# pe02.net
KiCad netlist of a schematic drawn in EAGLE
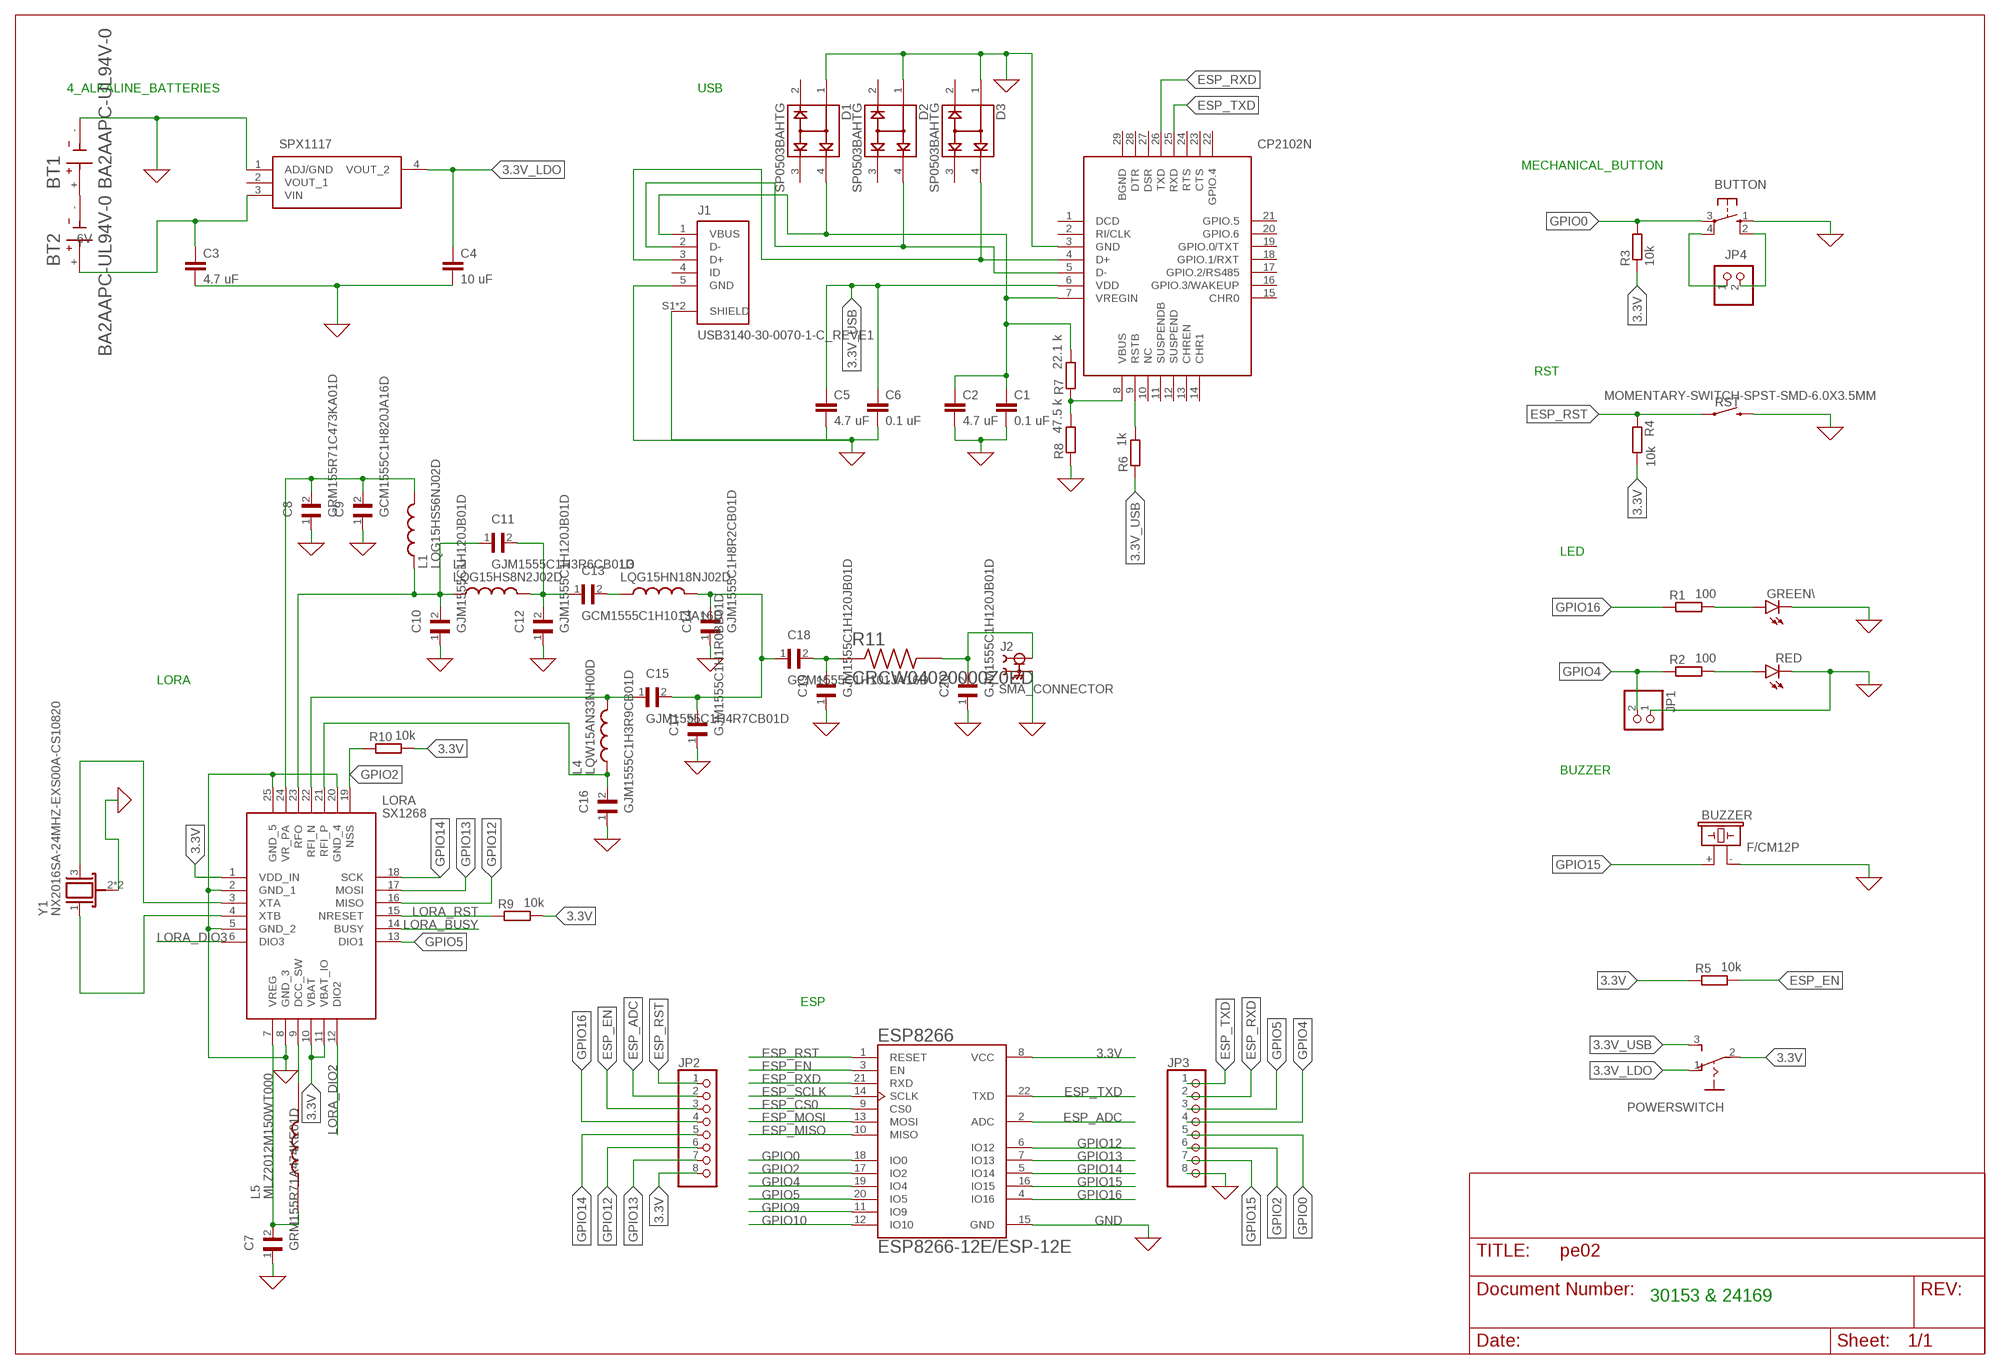
[diagram p0: schematic, sheet 1]

(export (version "E")
  (design (tool "Eeschema 10.0.6"))
  (components
    (comp (ref "BT1")
      (value "BA2AAPC-UL94V-0")
      (footprint "eagle-import:BAT_BA2AAPC-UL94V-0")
      (fields (field (name "MF") "MPD"))
      (libsource (lib "eagle-import") (part "BA2AAPC-UL94V-0"))
    )
    (comp (ref "BT2")
      (value "BA2AAPC-UL94V-0")
      (footprint "eagle-import:BAT_BA2AAPC-UL94V-0")
      (fields (field (name "MF") "MPD"))
      (libsource (lib "eagle-import") (part "BA2AAPC-UL94V-0"))
    )
    (comp (ref "BUTTON")
      (value "10-XX")
      (footprint "eagle-import:B3F-10XX")
      (fields (field (name "MPN") "B3F-1000"))
      (libsource (lib "eagle-import") (part "10-XX"))
    )
    (comp (ref "BUZZER")
      (value "F/CM12P")
      (footprint "eagle-import:F_CM12P")
      (libsource (lib "eagle-import") (part "F/CM12P"))
    )
    (comp (ref "C1")
      (value "0.1 uF")
      (footprint "eagle-import:C1206K")
      (libsource (lib "eagle-import") (part "C-EUC1206K"))
    )
    (comp (ref "C2")
      (value "4.7 uF")
      (footprint "eagle-import:C1206K")
      (libsource (lib "eagle-import") (part "C-EUC1206K"))
    )
    (comp (ref "C3")
      (value "4.7 uF")
      (footprint "eagle-import:C1206K")
      (libsource (lib "eagle-import") (part "C-EUC1206K"))
    )
    (comp (ref "C4")
      (value "10 uF")
      (footprint "eagle-import:C1206K")
      (libsource (lib "eagle-import") (part "C-EUC1206K"))
    )
    (comp (ref "C5")
      (value "4.7 uF")
      (footprint "eagle-import:C1206K")
      (libsource (lib "eagle-import") (part "C-EUC1206K"))
    )
    (comp (ref "C6")
      (value "0.1 uF")
      (footprint "eagle-import:C1206K")
      (libsource (lib "eagle-import") (part "C-EUC1206K"))
    )
    (comp (ref "C7")
      (value "GRM155R71A474KE01D")
      (footprint "eagle-import:CAPC1005X55N")
      (fields (field (name "MF") "Murata"))
      (libsource (lib "eagle-import") (part "GRM155R71A474KE01D"))
    )
    (comp (ref "C8")
      (value "GRM155R71C473KA01D")
      (footprint "eagle-import:CAPC1005X55N")
      (fields (field (name "MF") "Murata"))
      (libsource (lib "eagle-import") (part "GRM155R71C473KA01D"))
    )
    (comp (ref "C9")
      (value "GCM1555C1H820JA16D")
      (footprint "eagle-import:CAPC1005X55N")
      (fields (field (name "MF") "Murata Electronics"))
      (libsource (lib "eagle-import") (part "GCM1555C1H820JA16D"))
    )
    (comp (ref "C10")
      (value "GJM1555C1H120JB01D")
      (footprint "eagle-import:CAPC1005X55N")
      (fields (field (name "MF") "Murata"))
      (libsource (lib "eagle-import") (part "GJM1555C1H120JB01D"))
    )
    (comp (ref "C11")
      (value "GJM1555C1H3R6CB01D")
      (footprint "eagle-import:CAPC1005X55N")
      (fields (field (name "MF") "Murata"))
      (libsource (lib "eagle-import") (part "GJM1555C1H3R6CB01D"))
    )
    (comp (ref "C12")
      (value "GJM1555C1H120JB01D")
      (footprint "eagle-import:CAPC1005X55N")
      (fields (field (name "MF") "Murata"))
      (libsource (lib "eagle-import") (part "GJM1555C1H120JB01D"))
    )
    (comp (ref "C13")
      (value "GCM1555C1H101JA16D")
      (footprint "eagle-import:CAPC1005X55N")
      (fields (field (name "MF") "Murata Electronics"))
      (libsource (lib "eagle-import") (part "GCM1555C1H101JA16D"))
    )
    (comp (ref "C14")
      (value "GJM1555C1H8R2CB01D")
      (footprint "eagle-import:CAPC1005X55N")
      (fields (field (name "MF") "Murata"))
      (libsource (lib "eagle-import") (part "GJM1555C1H8R2CB01D"))
    )
    (comp (ref "C15")
      (value "GJM1555C1H4R7CB01D")
      (footprint "eagle-import:CAPC1005X55N")
      (fields (field (name "MF") "Murata"))
      (libsource (lib "eagle-import") (part "GJM1555C1H4R7CB01D"))
    )
    (comp (ref "C16")
      (value "GJM1555C1H3R9CB01D")
      (footprint "eagle-import:CAPC1005X55N")
      (fields (field (name "MF") "Murata"))
      (libsource (lib "eagle-import") (part "GJM1555C1H3R9CB01D"))
    )
    (comp (ref "C17")
      (value "GJM1555C1H1R0BB01D")
      (footprint "eagle-import:CAPC1005X55N")
      (fields (field (name "MF") "Murata"))
      (libsource (lib "eagle-import") (part "GJM1555C1H1R0BB01D"))
    )
    (comp (ref "C18")
      (value "GCM1555C1H101JA16D")
      (footprint "eagle-import:CAPC1005X55N")
      (fields (field (name "MF") "Murata Electronics"))
      (libsource (lib "eagle-import") (part "GCM1555C1H101JA16D"))
    )
    (comp (ref "C19")
      (value "GJM1555C1H120JB01D")
      (footprint "eagle-import:CAPC1005X55N")
      (fields (field (name "MF") "Murata"))
      (libsource (lib "eagle-import") (part "GJM1555C1H120JB01D"))
    )
    (comp (ref "C20")
      (value "GJM1555C1H120JB01D")
      (footprint "eagle-import:CAPC1005X55N")
      (fields (field (name "MF") "Murata"))
      (libsource (lib "eagle-import") (part "GJM1555C1H120JB01D"))
    )
    (comp (ref "CP2102N")
      (value "CP2102N-A02-GQFN28")
      (footprint "eagle-import:QFN50P500X500X80-29N")
      (fields (field (name "MOUSER_PART_NUMBER") "634-CP2102NA02GQFN28"))
      (libsource (lib "eagle-import") (part "CP2102N-A02-GQFN28"))
    )
    (comp (ref "D1")
      (value "SP0503BAHTG")
      (footprint "eagle-import:SOT143")
      (fields (field (name "MF") "Littelfuse Inc."))
      (libsource (lib "eagle-import") (part "SP0503BAHTG"))
    )
    (comp (ref "D2")
      (value "SP0503BAHTG")
      (footprint "eagle-import:SOT143")
      (fields (field (name "MF") "Littelfuse Inc."))
      (libsource (lib "eagle-import") (part "SP0503BAHTG"))
    )
    (comp (ref "D3")
      (value "SP0503BAHTG")
      (footprint "eagle-import:SOT143")
      (fields (field (name "MF") "Littelfuse Inc."))
      (libsource (lib "eagle-import") (part "SP0503BAHTG"))
    )
    (comp (ref "ESP8266")
      (value "ESP8266-12E/ESP-12E")
      (footprint "eagle-import:XCVR_ESP8266-12E_ESP-12E")
      (fields (field (name "MF") "AI-Thinker"))
      (libsource (lib "eagle-import") (part "ESP8266-12E/ESP-12E"))
    )
    (comp (ref "GREEN\\")
      (value "LEDCHIPLED_1206")
      (footprint "eagle-import:CHIPLED_1206")
      (libsource (lib "eagle-import") (part "LEDCHIPLED_1206"))
    )
    (comp (ref "J1")
      (value "USB3140-30-0070-1-C_REVE1")
      (footprint "eagle-import:GCT_USB3140-30-0070-1-C_REVE1")
      (fields (field (name "MF") "Global Connector Technology") (field (name "MP") "USB3140-30-0070-1-C"))
      (libsource (lib "eagle-import") (part "USB3140-30-0070-1-C_REVE1"))
    )
    (comp (ref "J2")
      (value "SMA_CONNECTOR")
      (footprint "eagle-import:LPRS_SMA_CONNECTOR")
      (fields (field (name "MF") "LPRS") (field (name "MP") "SMA CONNECTOR"))
      (libsource (lib "eagle-import") (part "SMA_CONNECTOR"))
    )
    (comp (ref "JP1")
      (value "PINHD-1X2")
      (footprint "eagle-import:1X02")
      (libsource (lib "eagle-import") (part "PINHD-1X2"))
    )
    (comp (ref "JP2")
      (value "PINHD-1X8")
      (footprint "eagle-import:1X08")
      (libsource (lib "eagle-import") (part "PINHD-1X8"))
    )
    (comp (ref "JP3")
      (value "PINHD-1X8")
      (footprint "eagle-import:1X08")
      (libsource (lib "eagle-import") (part "PINHD-1X8"))
    )
    (comp (ref "JP4")
      (value "PINHD-1X2")
      (footprint "eagle-import:1X02")
      (libsource (lib "eagle-import") (part "PINHD-1X2"))
    )
    (comp (ref "L1")
      (value "LQG15HS56NJ02D")
      (footprint "eagle-import:INDC1005X55N")
      (fields (field (name "MF") "Murata"))
      (libsource (lib "eagle-import") (part "LQG15HS56NJ02D"))
    )
    (comp (ref "L2")
      (value "LQG15HS8N2J02D")
      (footprint "eagle-import:INDC1005X55N")
      (fields (field (name "MF") "Murata"))
      (libsource (lib "eagle-import") (part "LQG15HS8N2J02D"))
    )
    (comp (ref "L3")
      (value "LQG15HN18NJ02D")
      (footprint "eagle-import:INDC1005X55N")
      (fields (field (name "MF") "Murata"))
      (libsource (lib "eagle-import") (part "LQG15HN18NJ02D"))
    )
    (comp (ref "L4")
      (value "LQW15AN33NH00D")
      (footprint "eagle-import:INDC1005X60N")
      (fields (field (name "MF") "Murata"))
      (libsource (lib "eagle-import") (part "LQW15AN33NH00D"))
    )
    (comp (ref "L5")
      (value "MLZ2012M150WT000")
      (footprint "eagle-import:INDC2012X145N")
      (fields (field (name "MF") "TDK Corporation"))
      (libsource (lib "eagle-import") (part "MLZ2012M150WT000"))
    )
    (comp (ref "LORA")
      (value "SX1268")
      (footprint "eagle-import:QFN50P400X400X100-25N")
      (libsource (lib "eagle-import") (part "SX1268"))
    )
    (comp (ref "POWERSWITCH")
      (value "255SB")
      (footprint "eagle-import:255SB")
      (libsource (lib "eagle-import") (part "255SB"))
    )
    (comp (ref "R1")
      (value "100")
      (footprint "eagle-import:R1206")
      (libsource (lib "eagle-import") (part "R-EU_R1206"))
    )
    (comp (ref "R2")
      (value "100")
      (footprint "eagle-import:R1206")
      (libsource (lib "eagle-import") (part "R-EU_R1206"))
    )
    (comp (ref "R3")
      (value "10k")
      (footprint "eagle-import:R1206")
      (libsource (lib "eagle-import") (part "R-EU_R1206"))
    )
    (comp (ref "R4")
      (value "10k")
      (footprint "eagle-import:R1206")
      (libsource (lib "eagle-import") (part "R-EU_R1206"))
    )
    (comp (ref "R5")
      (value "10k")
      (footprint "eagle-import:R1206")
      (libsource (lib "eagle-import") (part "R-EU_R1206"))
    )
    (comp (ref "R6")
      (value "1k")
      (footprint "eagle-import:R1206")
      (libsource (lib "eagle-import") (part "R-EU_R1206"))
    )
    (comp (ref "R7")
      (value "22.1 k")
      (footprint "eagle-import:R1206")
      (libsource (lib "eagle-import") (part "R-EU_R1206"))
    )
    (comp (ref "R8")
      (value "47.5 k")
      (footprint "eagle-import:R1206")
      (libsource (lib "eagle-import") (part "R-EU_R1206"))
    )
    (comp (ref "R9")
      (value "10k")
      (footprint "eagle-import:R1206")
      (libsource (lib "eagle-import") (part "R-EU_R1206"))
    )
    (comp (ref "R10")
      (value "10k")
      (footprint "eagle-import:R1206")
      (libsource (lib "eagle-import") (part "R-EU_R1206"))
    )
    (comp (ref "R11")
      (value "CRCW04020000Z0ED")
      (footprint "eagle-import:RESC1005X40N")
      (fields (field (name "MF") "Vishay"))
      (libsource (lib "eagle-import") (part "CRCW04020000Z0ED"))
    )
    (comp (ref "RED")
      (value "LEDCHIPLED_1206")
      (footprint "eagle-import:CHIPLED_1206")
      (libsource (lib "eagle-import") (part "LEDCHIPLED_1206"))
    )
    (comp (ref "RST")
      (value "MOMENTARY-SWITCH-SPST-SMD-6.0X3.5MM")
      (footprint "eagle-import:TACTILE_SWITCH_SMD_6.0X3.5MM")
      (libsource (lib "eagle-import") (part "MOMENTARY-SWITCH-SPST-SMD-6.0X3.5MM"))
    )
    (comp (ref "SPX1117")
      (value "SPX1117M3-L-3-3_TR")
      (footprint "eagle-import:SOT230P700X180-4N")
      (fields
        (field (name "ARROW_PART_NUMBER") "SPX1117M3-L-3-3/TR")
        (field (name "MOUSER_PART_NUMBER") "701-SPX1117M3-L-33TR")
      )
      (libsource (lib "eagle-import") (part "SPX1117M3-L-3-3_TR"))
    )
    (comp (ref "Y1")
      (value "NX2016SA-24MHZ-EXS00A-CS10820")
      (footprint "eagle-import:OSC_NX2016SA-24MHZ-EXS00A-CS10820")
      (fields (field (name "MF") "NDK America, Inc."))
      (libsource (lib "eagle-import") (part "NX2016SA-24MHZ-EXS00A-CS10820"))
    )
  )
  (nets
    (net (code "1") (name "/6V") (class "Default")
      (node (ref "BT2") (pin "+") (pinfunction "+_+") (pintype "passive"))
      (node (ref "C3") (pin "1") (pinfunction "1_1") (pintype "passive"))
      (node (ref "SPX1117") (pin "3") (pinfunction "VIN_3") (pintype "bidirectional"))
    )
    (net (code "2") (name "/BGND") (class "Default")
      (node (ref "CP2102N") (pin "29") (pinfunction "BGND_29") (pintype "power_in"))
    )
    (net (code "3") (name "/ESP_CS0") (class "Default")
      (node (ref "ESP8266") (pin "9") (pinfunction "CS0_9") (pintype "input"))
    )
    (net (code "4") (name "/ESP_MISO") (class "Default")
      (node (ref "ESP8266") (pin "10") (pinfunction "MISO_10") (pintype "bidirectional"))
    )
    (net (code "5") (name "/ESP_MOSI") (class "Default")
      (node (ref "ESP8266") (pin "13") (pinfunction "MOSI_13") (pintype "bidirectional"))
    )
    (net (code "6") (name "/ESP_SCLK") (class "Default")
      (node (ref "ESP8266") (pin "14") (pinfunction "SCLK_14") (pintype "input"))
    )
    (net (code "7") (name "/GPIO9") (class "Default")
      (node (ref "ESP8266") (pin "11") (pinfunction "IO9_11") (pintype "bidirectional"))
    )
    (net (code "8") (name "/GPIO10") (class "Default")
      (node (ref "ESP8266") (pin "12") (pinfunction "IO10_12") (pintype "bidirectional"))
    )
    (net (code "9") (name "/LORA_BUSY") (class "Default")
      (node (ref "LORA") (pin "14") (pinfunction "BUSY_14") (pintype "bidirectional"))
    )
    (net (code "10") (name "/LORA_DIO2") (class "Default")
      (node (ref "LORA") (pin "12") (pinfunction "DIO2_12") (pintype "bidirectional"))
    )
    (net (code "11") (name "/LORA_DIO3") (class "Default")
      (node (ref "LORA") (pin "6") (pinfunction "DIO3_6") (pintype "bidirectional"))
    )
    (net (code "12") (name "/LORA_RST") (class "Default")
      (node (ref "LORA") (pin "15") (pinfunction "NRESET_15") (pintype "bidirectional"))
      (node (ref "R9") (pin "1") (pinfunction "1_1") (pintype "passive"))
    )
    (net (code "13") (name "3.3V") (class "Default")
      (node (ref "ESP8266") (pin "8") (pinfunction "VCC_8") (pintype "power_in"))
      (node (ref "JP2") (pin "8") (pinfunction "8_8") (pintype "passive"))
      (node (ref "LORA") (pin "1") (pinfunction "VDD_IN_1") (pintype "bidirectional"))
      (node (ref "LORA") (pin "10") (pinfunction "VBAT_10") (pintype "bidirectional"))
      (node (ref "LORA") (pin "11") (pinfunction "VBAT_IO_11") (pintype "bidirectional"))
      (node (ref "POWERSWITCH") (pin "2") (pinfunction "P_2") (pintype "passive"))
      (node (ref "R10") (pin "2") (pinfunction "2_2") (pintype "passive"))
      (node (ref "R3") (pin "1") (pinfunction "1_1") (pintype "passive"))
      (node (ref "R4") (pin "2") (pinfunction "2_2") (pintype "passive"))
      (node (ref "R5") (pin "1") (pinfunction "1_1") (pintype "passive"))
      (node (ref "R9") (pin "2") (pinfunction "2_2") (pintype "passive"))
    )
    (net (code "14") (name "3.3V_LDO") (class "Default")
      (node (ref "C4") (pin "1") (pinfunction "1_1") (pintype "passive"))
      (node (ref "POWERSWITCH") (pin "1") (pinfunction "O_1") (pintype "passive"))
      (node (ref "SPX1117") (pin "4") (pinfunction "VOUT_2_4") (pintype "bidirectional"))
    )
    (net (code "15") (name "3.3V_USB") (class "Default")
      (node (ref "C5") (pin "1") (pinfunction "1_1") (pintype "passive"))
      (node (ref "C6") (pin "1") (pinfunction "1_1") (pintype "passive"))
      (node (ref "CP2102N") (pin "6") (pinfunction "VDD_6") (pintype "power_in"))
      (node (ref "POWERSWITCH") (pin "3") (pinfunction "S_3") (pintype "passive"))
      (node (ref "R6") (pin "1") (pinfunction "1_1") (pintype "passive"))
    )
    (net (code "16") (name "ESP_ADC") (class "Default")
      (node (ref "ESP8266") (pin "2") (pinfunction "ADC_2") (pintype "passive"))
      (node (ref "JP2") (pin "2") (pinfunction "2_2") (pintype "passive"))
    )
    (net (code "17") (name "ESP_EN") (class "Default")
      (node (ref "ESP8266") (pin "3") (pinfunction "EN_3") (pintype "input"))
      (node (ref "JP2") (pin "3") (pinfunction "3_3") (pintype "passive"))
      (node (ref "R5") (pin "2") (pinfunction "2_2") (pintype "passive"))
    )
    (net (code "18") (name "ESP_RST") (class "Default")
      (node (ref "ESP8266") (pin "1") (pinfunction "RESET_1") (pintype "input"))
      (node (ref "JP2") (pin "1") (pinfunction "1_1") (pintype "passive"))
      (node (ref "R4") (pin "1") (pinfunction "1_1") (pintype "passive"))
      (node (ref "RST") (pin "1") (pinfunction "1_1") (pintype "passive"))
    )
    (net (code "19") (name "ESP_RXD") (class "Default")
      (node (ref "CP2102N") (pin "26") (pinfunction "TXD_26") (pintype "output"))
      (node (ref "ESP8266") (pin "21") (pinfunction "RXD_21") (pintype "input"))
      (node (ref "JP3") (pin "2") (pinfunction "2_2") (pintype "passive"))
    )
    (net (code "20") (name "ESP_TXD") (class "Default")
      (node (ref "CP2102N") (pin "25") (pinfunction "RXD_25") (pintype "input"))
      (node (ref "ESP8266") (pin "22") (pinfunction "TXD_22") (pintype "output"))
      (node (ref "JP3") (pin "1") (pinfunction "1_1") (pintype "passive"))
    )
    (net (code "21") (name "GND") (class "Default")
      (node (ref "BT1") (pin "-") (pinfunction "-_-") (pintype "passive"))
      (node (ref "BUTTON") (pin "1") (pinfunction "S_1") (pintype "passive"))
      (node (ref "BUZZER") (pin "-") (pinfunction "2_-") (pintype "passive"))
      (node (ref "C1") (pin "2") (pinfunction "2_2") (pintype "passive"))
      (node (ref "C10") (pin "1") (pinfunction "1_1") (pintype "passive"))
      (node (ref "C12") (pin "1") (pinfunction "1_1") (pintype "passive"))
      (node (ref "C14") (pin "1") (pinfunction "1_1") (pintype "passive"))
      (node (ref "C16") (pin "1") (pinfunction "1_1") (pintype "passive"))
      (node (ref "C17") (pin "1") (pinfunction "1_1") (pintype "passive"))
      (node (ref "C19") (pin "1") (pinfunction "1_1") (pintype "passive"))
      (node (ref "C2") (pin "2") (pinfunction "2_2") (pintype "passive"))
      (node (ref "C20") (pin "1") (pinfunction "1_1") (pintype "passive"))
      (node (ref "C3") (pin "2") (pinfunction "2_2") (pintype "passive"))
      (node (ref "C4") (pin "2") (pinfunction "2_2") (pintype "passive"))
      (node (ref "C5") (pin "2") (pinfunction "2_2") (pintype "passive"))
      (node (ref "C6") (pin "2") (pinfunction "2_2") (pintype "passive"))
      (node (ref "C7") (pin "1") (pinfunction "1_1") (pintype "passive"))
      (node (ref "C8") (pin "1") (pinfunction "1_1") (pintype "passive"))
      (node (ref "C9") (pin "1") (pinfunction "1_1") (pintype "passive"))
      (node (ref "CP2102N") (pin "3") (pinfunction "GND_3") (pintype "power_in"))
      (node (ref "D1") (pin "1") (pinfunction "1_1") (pintype "passive"))
      (node (ref "D2") (pin "1") (pinfunction "1_1") (pintype "passive"))
      (node (ref "D3") (pin "1") (pinfunction "1_1") (pintype "passive"))
      (node (ref "ESP8266") (pin "15") (pinfunction "GND_15") (pintype "power_in"))
      (node (ref "GREEN\\") (pin "C") (pinfunction "C_C") (pintype "passive"))
      (node (ref "J1") (pin "5") (pinfunction "GND_5") (pintype "power_in"))
      (node (ref "J1") (pin "S1") (pinfunction "SHIELD_S1") (pintype "passive"))
      (node (ref "J1") (pin "S2") (pinfunction "SHIELD_S2") (pintype "passive"))
      (node (ref "J2") (pin "G1") (pinfunction "2_G1") (pintype "passive"))
      (node (ref "J2") (pin "G2") (pinfunction "2_G2") (pintype "passive"))
      (node (ref "J2") (pin "G3") (pinfunction "2_G3") (pintype "passive"))
      (node (ref "J2") (pin "G4") (pinfunction "2_G4") (pintype "passive"))
      (node (ref "JP1") (pin "1") (pinfunction "1_1") (pintype "passive"))
      (node (ref "JP3") (pin "8") (pinfunction "8_8") (pintype "passive"))
      (node (ref "LORA") (pin "2") (pinfunction "GND_1_2") (pintype "bidirectional"))
      (node (ref "LORA") (pin "20") (pinfunction "GND_4_20") (pintype "bidirectional"))
      (node (ref "LORA") (pin "25") (pinfunction "GND_5_25") (pintype "bidirectional"))
      (node (ref "LORA") (pin "5") (pinfunction "GND_2_5") (pintype "bidirectional"))
      (node (ref "LORA") (pin "8") (pinfunction "GND_3_8") (pintype "bidirectional"))
      (node (ref "R8") (pin "1") (pinfunction "1_1") (pintype "passive"))
      (node (ref "RED") (pin "C") (pinfunction "C_C") (pintype "passive"))
      (node (ref "RST") (pin "2") (pinfunction "2_2") (pintype "passive"))
      (node (ref "SPX1117") (pin "1") (pinfunction "ADJ/GND_1") (pintype "bidirectional"))
      (node (ref "Y1") (pin "2") (pinfunction "GND_2") (pintype "power_in"))
      (node (ref "Y1") (pin "4") (pinfunction "GND_4") (pintype "power_in"))
    )
    (net (code "22") (name "GPIO0") (class "Default")
      (node (ref "BUTTON") (pin "3") (pinfunction "P_3") (pintype "passive"))
      (node (ref "ESP8266") (pin "18") (pinfunction "IO0_18") (pintype "bidirectional"))
      (node (ref "JP3") (pin "5") (pinfunction "5_5") (pintype "passive"))
      (node (ref "R3") (pin "2") (pinfunction "2_2") (pintype "passive"))
    )
    (net (code "23") (name "GPIO2") (class "Default")
      (node (ref "ESP8266") (pin "17") (pinfunction "IO2_17") (pintype "bidirectional"))
      (node (ref "JP3") (pin "6") (pinfunction "6_6") (pintype "passive"))
      (node (ref "LORA") (pin "19") (pinfunction "NSS_19") (pintype "bidirectional"))
      (node (ref "R10") (pin "1") (pinfunction "1_1") (pintype "passive"))
    )
    (net (code "24") (name "GPIO4") (class "Default")
      (node (ref "ESP8266") (pin "19") (pinfunction "IO4_19") (pintype "bidirectional"))
      (node (ref "JP1") (pin "2") (pinfunction "2_2") (pintype "passive"))
      (node (ref "JP3") (pin "4") (pinfunction "4_4") (pintype "passive"))
      (node (ref "R2") (pin "1") (pinfunction "1_1") (pintype "passive"))
    )
    (net (code "25") (name "GPIO5") (class "Default")
      (node (ref "ESP8266") (pin "20") (pinfunction "IO5_20") (pintype "bidirectional"))
      (node (ref "JP3") (pin "3") (pinfunction "3_3") (pintype "passive"))
      (node (ref "LORA") (pin "13") (pinfunction "DIO1_13") (pintype "bidirectional"))
    )
    (net (code "26") (name "GPIO12") (class "Default")
      (node (ref "ESP8266") (pin "6") (pinfunction "IO12_6") (pintype "bidirectional"))
      (node (ref "JP2") (pin "6") (pinfunction "6_6") (pintype "passive"))
      (node (ref "LORA") (pin "16") (pinfunction "MISO_16") (pintype "bidirectional"))
    )
    (net (code "27") (name "GPIO13") (class "Default")
      (node (ref "ESP8266") (pin "7") (pinfunction "IO13_7") (pintype "bidirectional"))
      (node (ref "JP2") (pin "7") (pinfunction "7_7") (pintype "passive"))
      (node (ref "LORA") (pin "17") (pinfunction "MOSI_17") (pintype "bidirectional"))
    )
    (net (code "28") (name "GPIO14") (class "Default")
      (node (ref "ESP8266") (pin "5") (pinfunction "IO14_5") (pintype "bidirectional"))
      (node (ref "JP2") (pin "5") (pinfunction "5_5") (pintype "passive"))
      (node (ref "LORA") (pin "18") (pinfunction "SCK_18") (pintype "bidirectional"))
    )
    (net (code "29") (name "GPIO15") (class "Default")
      (node (ref "BUZZER") (pin "+") (pinfunction "1_+") (pintype "passive"))
      (node (ref "ESP8266") (pin "16") (pinfunction "IO15_16") (pintype "bidirectional"))
      (node (ref "JP3") (pin "7") (pinfunction "7_7") (pintype "passive"))
    )
    (net (code "30") (name "GPIO16") (class "Default")
      (node (ref "ESP8266") (pin "4") (pinfunction "IO16_4") (pintype "bidirectional"))
      (node (ref "JP2") (pin "4") (pinfunction "4_4") (pintype "passive"))
      (node (ref "R1") (pin "1") (pinfunction "1_1") (pintype "passive"))
    )
    (net (code "31") (name "Net-(BT1-Pad+)") (class "Default")
      (node (ref "BT1") (pin "+") (pinfunction "+_+") (pintype "passive"))
      (node (ref "BT2") (pin "-") (pinfunction "-_-") (pintype "passive"))
    )
    (net (code "32") (name "Net-(BUTTON-P1)") (class "Default")
      (node (ref "BUTTON") (pin "4") (pinfunction "P1_4") (pintype "passive"))
      (node (ref "JP4") (pin "1") (pinfunction "1_1") (pintype "passive"))
    )
    (net (code "33") (name "Net-(BUTTON-S1)") (class "Default")
      (node (ref "BUTTON") (pin "2") (pinfunction "S1_2") (pintype "passive"))
      (node (ref "JP4") (pin "2") (pinfunction "2_2") (pintype "passive"))
    )
    (net (code "34") (name "Net-(C11-Pad2)") (class "Default")
      (node (ref "C11") (pin "2") (pinfunction "2_2") (pintype "passive"))
      (node (ref "C12") (pin "2") (pinfunction "2_2") (pintype "passive"))
      (node (ref "C13") (pin "1") (pinfunction "1_1") (pintype "passive"))
      (node (ref "L2") (pin "2") (pinfunction "2_2") (pintype "passive"))
    )
    (net (code "35") (name "Net-(C13-Pad2)") (class "Default")
      (node (ref "C13") (pin "2") (pinfunction "2_2") (pintype "passive"))
      (node (ref "L3") (pin "1") (pinfunction "1_1") (pintype "passive"))
    )
    (net (code "36") (name "Net-(C14-Pad2)") (class "Default")
      (node (ref "C14") (pin "2") (pinfunction "2_2") (pintype "passive"))
      (node (ref "C15") (pin "2") (pinfunction "2_2") (pintype "passive"))
      (node (ref "C17") (pin "2") (pinfunction "2_2") (pintype "passive"))
      (node (ref "C18") (pin "1") (pinfunction "1_1") (pintype "passive"))
      (node (ref "L3") (pin "2") (pinfunction "2_2") (pintype "passive"))
    )
    (net (code "37") (name "Net-(C18-Pad2)") (class "Default")
      (node (ref "C18") (pin "2") (pinfunction "2_2") (pintype "passive"))
      (node (ref "C19") (pin "2") (pinfunction "2_2") (pintype "passive"))
      (node (ref "R11") (pin "1") (pinfunction "1_1") (pintype "passive"))
    )
    (net (code "38") (name "Net-(C20-Pad2)") (class "Default")
      (node (ref "C20") (pin "2") (pinfunction "2_2") (pintype "passive"))
      (node (ref "J2") (pin "1") (pinfunction "1_1") (pintype "passive"))
      (node (ref "R11") (pin "2") (pinfunction "2_2") (pintype "passive"))
    )
    (net (code "39") (name "Net-(CP2102N-D+)") (class "Default")
      (node (ref "CP2102N") (pin "4") (pinfunction "D+_4") (pintype "bidirectional"))
      (node (ref "D3") (pin "4") (pinfunction "4_4") (pintype "passive"))
      (node (ref "J1") (pin "3") (pinfunction "D+_3") (pintype "bidirectional"))
    )
    (net (code "40") (name "Net-(CP2102N-D-)") (class "Default")
      (node (ref "CP2102N") (pin "5") (pinfunction "D-_5") (pintype "bidirectional"))
      (node (ref "D2") (pin "4") (pinfunction "4_4") (pintype "passive"))
      (node (ref "J1") (pin "2") (pinfunction "D-_2") (pintype "bidirectional"))
    )
    (net (code "41") (name "Net-(CP2102N-RSTB)") (class "Default")
      (node (ref "CP2102N") (pin "9") (pinfunction "RSTB_9") (pintype "input"))
      (node (ref "R6") (pin "2") (pinfunction "2_2") (pintype "passive"))
    )
    (net (code "42") (name "Net-(CP2102N-VBUS)") (class "Default")
      (node (ref "CP2102N") (pin "8") (pinfunction "VBUS_8") (pintype "input"))
      (node (ref "R7") (pin "1") (pinfunction "1_1") (pintype "passive"))
      (node (ref "R8") (pin "2") (pinfunction "2_2") (pintype "passive"))
    )
    (net (code "43") (name "Net-(CP2102N-VREGIN)") (class "Default")
      (node (ref "C1") (pin "1") (pinfunction "1_1") (pintype "passive"))
      (node (ref "C2") (pin "1") (pinfunction "1_1") (pintype "passive"))
      (node (ref "CP2102N") (pin "7") (pinfunction "VREGIN_7") (pintype "power_in"))
      (node (ref "D1") (pin "4") (pinfunction "4_4") (pintype "passive"))
      (node (ref "J1") (pin "1") (pinfunction "VBUS_1") (pintype "power_in"))
      (node (ref "R7") (pin "2") (pinfunction "2_2") (pintype "passive"))
    )
    (net (code "44") (name "Net-(GREEN\\-PadA)") (class "Default")
      (node (ref "GREEN\\") (pin "A") (pinfunction "A_A") (pintype "passive"))
      (node (ref "R1") (pin "2") (pinfunction "2_2") (pintype "passive"))
    )
    (net (code "45") (name "Net-(LORA-DCC_SW)") (class "Default")
      (node (ref "L5") (pin "2") (pinfunction "2_2") (pintype "passive"))
      (node (ref "LORA") (pin "9") (pinfunction "DCC_SW_9") (pintype "bidirectional"))
    )
    (net (code "46") (name "Net-(LORA-RFI_N)") (class "Default")
      (node (ref "C15") (pin "1") (pinfunction "1_1") (pintype "passive"))
      (node (ref "L4") (pin "2") (pinfunction "2_2") (pintype "passive"))
      (node (ref "LORA") (pin "22") (pinfunction "RFI_N_22") (pintype "bidirectional"))
    )
    (net (code "47") (name "Net-(LORA-RFI_P)") (class "Default")
      (node (ref "C16") (pin "2") (pinfunction "2_2") (pintype "passive"))
      (node (ref "L4") (pin "1") (pinfunction "1_1") (pintype "passive"))
      (node (ref "LORA") (pin "21") (pinfunction "RFI_P_21") (pintype "bidirectional"))
    )
    (net (code "48") (name "Net-(LORA-RFO)") (class "Default")
      (node (ref "C10") (pin "2") (pinfunction "2_2") (pintype "passive"))
      (node (ref "C11") (pin "1") (pinfunction "1_1") (pintype "passive"))
      (node (ref "L1") (pin "1") (pinfunction "1_1") (pintype "passive"))
      (node (ref "L2") (pin "1") (pinfunction "1_1") (pintype "passive"))
      (node (ref "LORA") (pin "23") (pinfunction "RFO_23") (pintype "bidirectional"))
    )
    (net (code "49") (name "Net-(LORA-VREG)") (class "Default")
      (node (ref "C7") (pin "2") (pinfunction "2_2") (pintype "passive"))
      (node (ref "L5") (pin "1") (pinfunction "1_1") (pintype "passive"))
      (node (ref "LORA") (pin "7") (pinfunction "VREG_7") (pintype "bidirectional"))
    )
    (net (code "50") (name "Net-(LORA-VR_PA)") (class "Default")
      (node (ref "C8") (pin "2") (pinfunction "2_2") (pintype "passive"))
      (node (ref "C9") (pin "2") (pinfunction "2_2") (pintype "passive"))
      (node (ref "L1") (pin "2") (pinfunction "2_2") (pintype "passive"))
      (node (ref "LORA") (pin "24") (pinfunction "VR_PA_24") (pintype "bidirectional"))
    )
    (net (code "51") (name "Net-(LORA-XTA)") (class "Default")
      (node (ref "LORA") (pin "3") (pinfunction "XTA_3") (pintype "bidirectional"))
      (node (ref "Y1") (pin "3") (pinfunction "3_3") (pintype "passive"))
    )
    (net (code "52") (name "Net-(LORA-XTB)") (class "Default")
      (node (ref "LORA") (pin "4") (pinfunction "XTB_4") (pintype "bidirectional"))
      (node (ref "Y1") (pin "1") (pinfunction "1_1") (pintype "passive"))
    )
    (net (code "53") (name "Net-(R2-Pad2)") (class "Default")
      (node (ref "R2") (pin "2") (pinfunction "2_2") (pintype "passive"))
      (node (ref "RED") (pin "A") (pinfunction "A_A") (pintype "passive"))
    )
    (net (code "54") (name "unconnected-(CP2102N-CHR0-Pad15)") (class "Default")
      (node (ref "CP2102N") (pin "15") (pinfunction "CHR0_15") (pintype "output"))
    )
    (net (code "55") (name "unconnected-(CP2102N-CHR1-Pad14)") (class "Default")
      (node (ref "CP2102N") (pin "14") (pinfunction "CHR1_14") (pintype "output"))
    )
    (net (code "56") (name "unconnected-(CP2102N-CHREN-Pad13)") (class "Default")
      (node (ref "CP2102N") (pin "13") (pinfunction "CHREN_13") (pintype "output"))
    )
    (net (code "57") (name "unconnected-(CP2102N-CTS-Pad23)") (class "Default")
      (node (ref "CP2102N") (pin "23") (pinfunction "CTS_23") (pintype "input"))
    )
    (net (code "58") (name "unconnected-(CP2102N-DCD-Pad1)") (class "Default")
      (node (ref "CP2102N") (pin "1") (pinfunction "DCD_1") (pintype "input"))
    )
    (net (code "59") (name "unconnected-(CP2102N-DSR-Pad27)") (class "Default")
      (node (ref "CP2102N") (pin "27") (pinfunction "DSR_27") (pintype "input"))
    )
    (net (code "60") (name "unconnected-(CP2102N-DTR-Pad28)") (class "Default")
      (node (ref "CP2102N") (pin "28") (pinfunction "DTR_28") (pintype "output"))
    )
    (net (code "61") (name "unconnected-(CP2102N-GPIO.0{slash}TXT-Pad19)") (class "Default")
      (node (ref "CP2102N") (pin "19") (pinfunction "GPIO.0/TXT_19") (pintype "bidirectional"))
    )
    (net (code "62") (name "unconnected-(CP2102N-GPIO.1{slash}RXT-Pad18)") (class "Default")
      (node (ref "CP2102N") (pin "18") (pinfunction "GPIO.1/RXT_18") (pintype "bidirectional"))
    )
    (net (code "63") (name "unconnected-(CP2102N-GPIO.2{slash}RS485-Pad17)") (class "Default")
      (node (ref "CP2102N") (pin "17") (pinfunction "GPIO.2/RS485_17") (pintype "bidirectional"))
    )
    (net (code "64") (name "unconnected-(CP2102N-GPIO.3{slash}WAKEUP-Pad16)") (class "Default")
      (node (ref "CP2102N") (pin "16") (pinfunction "GPIO.3/WAKEUP_16") (pintype "bidirectional"))
    )
    (net (code "65") (name "unconnected-(CP2102N-GPIO.4-Pad22)") (class "Default")
      (node (ref "CP2102N") (pin "22") (pinfunction "GPIO.4_22") (pintype "bidirectional"))
    )
    (net (code "66") (name "unconnected-(CP2102N-GPIO.5-Pad21)") (class "Default")
      (node (ref "CP2102N") (pin "21") (pinfunction "GPIO.5_21") (pintype "bidirectional"))
    )
    (net (code "67") (name "unconnected-(CP2102N-GPIO.6-Pad20)") (class "Default")
      (node (ref "CP2102N") (pin "20") (pinfunction "GPIO.6_20") (pintype "bidirectional"))
    )
    (net (code "68") (name "unconnected-(CP2102N-NC-Pad10)") (class "Default")
      (node (ref "CP2102N") (pin "10") (pinfunction "NC_10") (pintype "no_connect"))
    )
    (net (code "69") (name "unconnected-(CP2102N-RI{slash}CLK-Pad2)") (class "Default")
      (node (ref "CP2102N") (pin "2") (pinfunction "RI/CLK_2") (pintype "bidirectional"))
    )
    (net (code "70") (name "unconnected-(CP2102N-RTS-Pad24)") (class "Default")
      (node (ref "CP2102N") (pin "24") (pinfunction "RTS_24") (pintype "output"))
    )
    (net (code "71") (name "unconnected-(CP2102N-SUSPEND-Pad12)") (class "Default")
      (node (ref "CP2102N") (pin "12") (pinfunction "SUSPEND_12") (pintype "output"))
    )
    (net (code "72") (name "unconnected-(CP2102N-SUSPENDB-Pad11)") (class "Default")
      (node (ref "CP2102N") (pin "11") (pinfunction "SUSPENDB_11") (pintype "output"))
    )
    (net (code "73") (name "unconnected-(D1-Pad2)") (class "Default")
      (node (ref "D1") (pin "2") (pinfunction "2_2") (pintype "passive"))
    )
    (net (code "74") (name "unconnected-(D1-Pad3)") (class "Default")
      (node (ref "D1") (pin "3") (pinfunction "3_3") (pintype "passive"))
    )
    (net (code "75") (name "unconnected-(D2-Pad2)") (class "Default")
      (node (ref "D2") (pin "2") (pinfunction "2_2") (pintype "passive"))
    )
    (net (code "76") (name "unconnected-(D2-Pad3)") (class "Default")
      (node (ref "D2") (pin "3") (pinfunction "3_3") (pintype "passive"))
    )
    (net (code "77") (name "unconnected-(D3-Pad2)") (class "Default")
      (node (ref "D3") (pin "2") (pinfunction "2_2") (pintype "passive"))
    )
    (net (code "78") (name "unconnected-(D3-Pad3)") (class "Default")
      (node (ref "D3") (pin "3") (pinfunction "3_3") (pintype "passive"))
    )
    (net (code "79") (name "unconnected-(J1-ID-Pad4)") (class "Default")
      (node (ref "J1") (pin "4") (pinfunction "ID_4") (pintype "passive"))
    )
    (net (code "80") (name "unconnected-(SPX1117-VOUT_1-Pad2)") (class "Default")
      (node (ref "SPX1117") (pin "2") (pinfunction "VOUT_1_2") (pintype "bidirectional"))
    )
  )
)
